# schematics_2025-02-16.net
KiCad netlist of a schematic drawn in Altium Designer
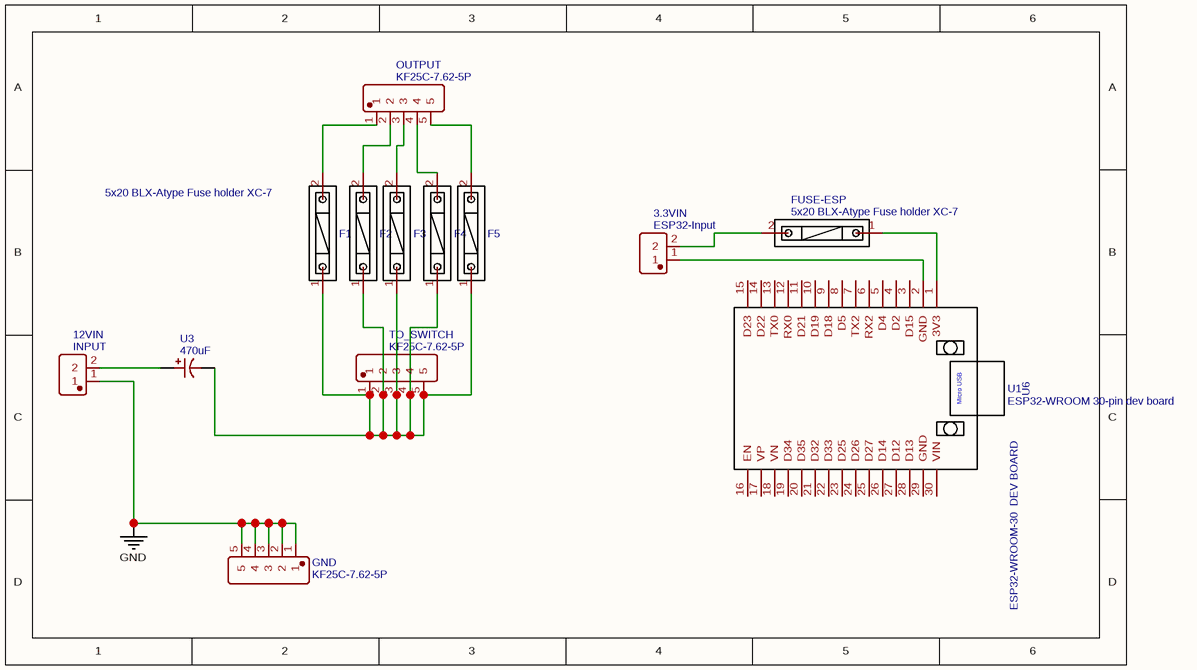
[diagram p0: schematics_2025-02-16.schdoc]

(export (version "E")
  (design (tool "Eeschema 10.0.6"))
  (components
    (comp (ref "3.3VIN")
      (value "ESP32-Input")
      (fields
        (field (name "MANUFACTURER") "KEFA(科发)")
        (field (name "MANUFACTURER PART") "KF25H-7.62-2P")
        (field (name "CONTRIBUTOR") "LCSC")
      )
      (libsource (lib "altium-import") (part "root_2_ESP32-Input_"))
    )
    (comp (ref "12VIN")
      (value "INPUT")
      (fields
        (field (name "MANUFACTURER") "KEFA(科发)")
        (field (name "MANUFACTURER PART") "KF25H-7.62-2P")
        (field (name "CONTRIBUTOR") "LCSC")
      )
      (libsource (lib "altium-import") (part "root_2_INPUT_"))
    )
    (comp (ref "F1")
      (value "5x20 BLX-Atype Fuse holder XC-7")
      (fields
        (field (name "MANUFACTURER PART") "5x20 BLX-A型 保险丝支架 XC-7")
        (field (name "MANUFACTURER") "xcfuse(旭程)")
      )
      (libsource (lib "altium-import") (part "root_1_5x20 BLX-Atype Fuse holder XC-7_"))
    )
    (comp (ref "F2")
      (value "5x20 BLX-Atype Fuse holder XC-7")
      (fields
        (field (name "MANUFACTURER PART") "5x20 BLX-A型 保险丝支架 XC-7")
        (field (name "MANUFACTURER") "xcfuse(旭程)")
      )
      (libsource (lib "altium-import") (part "root_1_5x20 BLX-Atype Fuse holder XC-7_"))
    )
    (comp (ref "F3")
      (value "5x20 BLX-Atype Fuse holder XC-7")
      (fields
        (field (name "MANUFACTURER PART") "5x20 BLX-A型 保险丝支架 XC-7")
        (field (name "MANUFACTURER") "xcfuse(旭程)")
      )
      (libsource (lib "altium-import") (part "root_1_5x20 BLX-Atype Fuse holder XC-7_"))
    )
    (comp (ref "F4")
      (value "5x20 BLX-Atype Fuse holder XC-7")
      (fields
        (field (name "MANUFACTURER PART") "5x20 BLX-A型 保险丝支架 XC-7")
        (field (name "MANUFACTURER") "xcfuse(旭程)")
      )
      (libsource (lib "altium-import") (part "root_1_5x20 BLX-Atype Fuse holder XC-7_"))
    )
    (comp (ref "F5")
      (value "5x20 BLX-Atype Fuse holder XC-7")
      (fields
        (field (name "MANUFACTURER PART") "5x20 BLX-A型 保险丝支架 XC-7")
        (field (name "MANUFACTURER") "xcfuse(旭程)")
      )
      (libsource (lib "altium-import") (part "root_1_5x20 BLX-Atype Fuse holder XC-7_"))
    )
    (comp (ref "FUSE-ESP")
      (value "5x20 BLX-Atype Fuse holder XC-7")
      (fields
        (field (name "MANUFACTURER PART") "5x20 BLX-A型 保险丝支架 XC-7")
        (field (name "MANUFACTURER") "xcfuse(旭程)")
      )
      (libsource (lib "altium-import") (part "root_2_5x20 BLX-Atype Fuse holder XC-7_"))
    )
    (comp (ref "GND")
      (value "KF25C-7.62-5P")
      (fields (field (name "MANUFACTURER") "KEFA(科发)") (field (name "CONTRIBUTOR") "LCSC"))
      (libsource (lib "altium-import") (part "root_3_KF25C-7.62-5P_"))
    )
    (comp (ref "OUTPUT")
      (value "KF25C-7.62-5P")
      (fields (field (name "MANUFACTURER") "KEFA(科发)") (field (name "CONTRIBUTOR") "LCSC"))
      (libsource (lib "altium-import") (part "root_1_KF25C-7.62-5P_"))
    )
    (comp (ref "TO_SWITCH")
      (value "KF25C-7.62-5P")
      (fields (field (name "MANUFACTURER") "KEFA(科发)") (field (name "CONTRIBUTOR") "LCSC"))
      (libsource (lib "altium-import") (part "root_1_KF25C-7.62-5P_"))
    )
    (comp (ref "U1")
      (value "ESP32-WROOM 30-pin dev board")
      (fields (field (name "CONTRIBUTOR") "viana7339"))
      (libsource (lib "altium-import") (part "root_3_ESP32-WROOM 30-pin dev board_"))
    )
    (comp (ref "U3")
      (value "470uF")
      (fields
        (field (name "MANUFACTURER") "KNSCHA(科尼盛)")
        (field (name "MANUFACTURER PART") "VT470UF16V167RV0135")
        (field (name "CONTRIBUTOR") "lcsc")
      )
      (libsource (lib "altium-import") (part "root_0_470uF_"))
    )
  )
  (nets
    (net (code "1") (name "GND") (class "Default")
      (node (ref "12VIN") (pin "1") (pinfunction "1_1") (pintype "passive"))
      (node (ref "GND") (pin "1") (pinfunction "1_1") (pintype "passive"))
      (node (ref "GND") (pin "2") (pinfunction "2_2") (pintype "passive"))
      (node (ref "GND") (pin "3") (pinfunction "3_3") (pintype "passive"))
      (node (ref "GND") (pin "4") (pinfunction "4_4") (pintype "passive"))
      (node (ref "GND") (pin "5") (pinfunction "5_5") (pintype "passive"))
    )
    (net (code "2") (name "Net-(3.3VIN-Pad1)") (class "Default")
      (node (ref "3.3VIN") (pin "1") (pinfunction "1_1") (pintype "passive"))
      (node (ref "U1") (pin "2") (pinfunction "GND_2") (pintype "passive"))
    )
    (net (code "3") (name "Net-(3.3VIN-Pad2)") (class "Default")
      (node (ref "3.3VIN") (pin "2") (pinfunction "2_2") (pintype "passive"))
      (node (ref "FUSE-ESP") (pin "2") (pinfunction "2_2") (pintype "passive"))
    )
    (net (code "4") (name "Net-(12VIN-Pad2)") (class "Default")
      (node (ref "12VIN") (pin "2") (pinfunction "2_2") (pintype "passive"))
      (node (ref "U3") (pin "1") (pinfunction "1_1") (pintype "passive"))
    )
    (net (code "5") (name "Net-(F1-Pad1)") (class "Default")
      (node (ref "F1") (pin "1") (pinfunction "1_1") (pintype "passive"))
      (node (ref "F2") (pin "1") (pinfunction "1_1") (pintype "passive"))
      (node (ref "F3") (pin "1") (pinfunction "1_1") (pintype "passive"))
      (node (ref "F4") (pin "1") (pinfunction "1_1") (pintype "passive"))
      (node (ref "F5") (pin "1") (pinfunction "1_1") (pintype "passive"))
      (node (ref "TO_SWITCH") (pin "1") (pinfunction "1_1") (pintype "passive"))
      (node (ref "TO_SWITCH") (pin "2") (pinfunction "2_2") (pintype "passive"))
      (node (ref "TO_SWITCH") (pin "3") (pinfunction "3_3") (pintype "passive"))
      (node (ref "TO_SWITCH") (pin "4") (pinfunction "4_4") (pintype "passive"))
      (node (ref "TO_SWITCH") (pin "5") (pinfunction "5_5") (pintype "passive"))
      (node (ref "U3") (pin "2") (pinfunction "2_2") (pintype "passive"))
    )
    (net (code "6") (name "Net-(F1-Pad2)") (class "Default")
      (node (ref "F1") (pin "2") (pinfunction "2_2") (pintype "passive"))
      (node (ref "OUTPUT") (pin "1") (pinfunction "1_1") (pintype "passive"))
    )
    (net (code "7") (name "Net-(F2-Pad2)") (class "Default")
      (node (ref "F2") (pin "2") (pinfunction "2_2") (pintype "passive"))
      (node (ref "OUTPUT") (pin "2") (pinfunction "2_2") (pintype "passive"))
    )
    (net (code "8") (name "Net-(F3-Pad2)") (class "Default")
      (node (ref "F3") (pin "2") (pinfunction "2_2") (pintype "passive"))
      (node (ref "OUTPUT") (pin "3") (pinfunction "3_3") (pintype "passive"))
    )
    (net (code "9") (name "Net-(F4-Pad2)") (class "Default")
      (node (ref "F4") (pin "2") (pinfunction "2_2") (pintype "passive"))
      (node (ref "OUTPUT") (pin "4") (pinfunction "4_4") (pintype "passive"))
    )
    (net (code "10") (name "Net-(F5-Pad2)") (class "Default")
      (node (ref "F5") (pin "2") (pinfunction "2_2") (pintype "passive"))
      (node (ref "OUTPUT") (pin "5") (pinfunction "5_5") (pintype "passive"))
    )
    (net (code "11") (name "Net-(U1-3V3)") (class "Default")
      (node (ref "FUSE-ESP") (pin "1") (pinfunction "1_1") (pintype "passive"))
      (node (ref "U1") (pin "1") (pinfunction "3V3_1") (pintype "passive"))
    )
    (net (code "12") (name "unconnected-(U1-D2-Pad4)") (class "Default")
      (node (ref "U1") (pin "4") (pinfunction "D2_4") (pintype "passive"))
    )
    (net (code "13") (name "unconnected-(U1-D4-Pad5)") (class "Default")
      (node (ref "U1") (pin "5") (pinfunction "D4_5") (pintype "passive"))
    )
    (net (code "14") (name "unconnected-(U1-D5-Pad8)") (class "Default")
      (node (ref "U1") (pin "8") (pinfunction "D5_8") (pintype "passive"))
    )
    (net (code "15") (name "unconnected-(U1-D12-Pad27)") (class "Default")
      (node (ref "U1") (pin "27") (pinfunction "D12_27") (pintype "passive"))
    )
    (net (code "16") (name "unconnected-(U1-D13-Pad28)") (class "Default")
      (node (ref "U1") (pin "28") (pinfunction "D13_28") (pintype "passive"))
    )
    (net (code "17") (name "unconnected-(U1-D14-Pad26)") (class "Default")
      (node (ref "U1") (pin "26") (pinfunction "D14_26") (pintype "passive"))
    )
    (net (code "18") (name "unconnected-(U1-D15-Pad3)") (class "Default")
      (node (ref "U1") (pin "3") (pinfunction "D15_3") (pintype "passive"))
    )
    (net (code "19") (name "unconnected-(U1-D18-Pad9)") (class "Default")
      (node (ref "U1") (pin "9") (pinfunction "D18_9") (pintype "passive"))
    )
    (net (code "20") (name "unconnected-(U1-D19-Pad10)") (class "Default")
      (node (ref "U1") (pin "10") (pinfunction "D19_10") (pintype "passive"))
    )
    (net (code "21") (name "unconnected-(U1-D21-Pad11)") (class "Default")
      (node (ref "U1") (pin "11") (pinfunction "D21_11") (pintype "passive"))
    )
    (net (code "22") (name "unconnected-(U1-D22-Pad14)") (class "Default")
      (node (ref "U1") (pin "14") (pinfunction "D22_14") (pintype "passive"))
    )
    (net (code "23") (name "unconnected-(U1-D23-Pad15)") (class "Default")
      (node (ref "U1") (pin "15") (pinfunction "D23_15") (pintype "passive"))
    )
    (net (code "24") (name "unconnected-(U1-D25-Pad23)") (class "Default")
      (node (ref "U1") (pin "23") (pinfunction "D25_23") (pintype "passive"))
    )
    (net (code "25") (name "unconnected-(U1-D26-Pad24)") (class "Default")
      (node (ref "U1") (pin "24") (pinfunction "D26_24") (pintype "passive"))
    )
    (net (code "26") (name "unconnected-(U1-D27-Pad25)") (class "Default")
      (node (ref "U1") (pin "25") (pinfunction "D27_25") (pintype "passive"))
    )
    (net (code "27") (name "unconnected-(U1-D32-Pad21)") (class "Default")
      (node (ref "U1") (pin "21") (pinfunction "D32_21") (pintype "passive"))
    )
    (net (code "28") (name "unconnected-(U1-D33-Pad22)") (class "Default")
      (node (ref "U1") (pin "22") (pinfunction "D33_22") (pintype "passive"))
    )
    (net (code "29") (name "unconnected-(U1-D34-Pad19)") (class "Default")
      (node (ref "U1") (pin "19") (pinfunction "D34_19") (pintype "passive"))
    )
    (net (code "30") (name "unconnected-(U1-D35-Pad20)") (class "Default")
      (node (ref "U1") (pin "20") (pinfunction "D35_20") (pintype "passive"))
    )
    (net (code "31") (name "unconnected-(U1-EN-Pad16)") (class "Default")
      (node (ref "U1") (pin "16") (pinfunction "EN_16") (pintype "passive"))
    )
    (net (code "32") (name "unconnected-(U1-GND-Pad29)") (class "Default")
      (node (ref "U1") (pin "29") (pinfunction "GND_29") (pintype "passive"))
    )
    (net (code "33") (name "unconnected-(U1-RX0-Pad12)") (class "Default")
      (node (ref "U1") (pin "12") (pinfunction "RX0_12") (pintype "passive"))
    )
    (net (code "34") (name "unconnected-(U1-RX2-Pad6)") (class "Default")
      (node (ref "U1") (pin "6") (pinfunction "RX2_6") (pintype "passive"))
    )
    (net (code "35") (name "unconnected-(U1-TX0-Pad13)") (class "Default")
      (node (ref "U1") (pin "13") (pinfunction "TX0_13") (pintype "passive"))
    )
    (net (code "36") (name "unconnected-(U1-TX2-Pad7)") (class "Default")
      (node (ref "U1") (pin "7") (pinfunction "TX2_7") (pintype "passive"))
    )
    (net (code "37") (name "unconnected-(U1-VIN-Pad30)") (class "Default")
      (node (ref "U1") (pin "30") (pinfunction "VIN_30") (pintype "passive"))
    )
    (net (code "38") (name "unconnected-(U1-VN-Pad18)") (class "Default")
      (node (ref "U1") (pin "18") (pinfunction "VN_18") (pintype "passive"))
    )
    (net (code "39") (name "unconnected-(U1-VP-Pad17)") (class "Default")
      (node (ref "U1") (pin "17") (pinfunction "VP_17") (pintype "passive"))
    )
  )
)
